# RFP.net
KiCad netlist of a schematic drawn in EAGLE
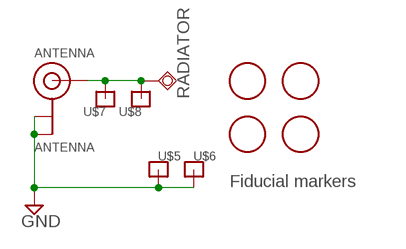
[diagram p0: schematic, sheet 1]

(export (version "E")
  (design (tool "Eeschema 10.0.6"))
  (components
    (comp (ref "ANTENNA")
      (value "ANTENNA")
      (footprint "eagle-import:U.FL")
      (libsource (lib "eagle-import") (part "ANTENNA_U.FL"))
    )
    (comp (ref "FD1")
      (value "FIDUCIAL")
      (footprint "eagle-import:FIDUCIAL_1MM")
      (libsource (lib "eagle-import") (part "FIDUCIAL"))
    )
    (comp (ref "FD2")
      (value "FIDUCIAL")
      (footprint "eagle-import:FIDUCIAL_1MM")
      (libsource (lib "eagle-import") (part "FIDUCIAL"))
    )
    (comp (ref "FD3")
      (value "FIDUCIAL")
      (footprint "eagle-import:FIDUCIAL_1MM")
      (libsource (lib "eagle-import") (part "FIDUCIAL"))
    )
    (comp (ref "FD4")
      (value "FIDUCIAL")
      (footprint "eagle-import:FIDUCIAL_1MM")
      (libsource (lib "eagle-import") (part "FIDUCIAL"))
    )
    (comp (ref "RADIATOR")
      (value "TPSQTP20SQ")
      (footprint "eagle-import:TP20SQ")
      (libsource (lib "eagle-import") (part "TPSQTP20SQ"))
    )
    (comp (ref "U$5")
      (value "2MMPILLAR")
      (footprint "eagle-import:2MMPILLAR")
      (libsource (lib "eagle-import") (part "2MMPILLAR"))
    )
    (comp (ref "U$6")
      (value "2MMPILLAR")
      (footprint "eagle-import:2MMPILLAR")
      (libsource (lib "eagle-import") (part "2MMPILLAR"))
    )
    (comp (ref "U$7")
      (value "2MMPILLAR")
      (footprint "eagle-import:2MMPILLAR")
      (libsource (lib "eagle-import") (part "2MMPILLAR"))
    )
    (comp (ref "U$8")
      (value "2MMPILLAR")
      (footprint "eagle-import:2MMPILLAR")
      (libsource (lib "eagle-import") (part "2MMPILLAR"))
    )
  )
  (nets
    (net (code "1") (name "GND") (class "Default")
      (node (ref "ANTENNA") (pin "1") (pinfunction "GND_1") (pintype "passive"))
      (node (ref "ANTENNA") (pin "2") (pinfunction "GND_2") (pintype "passive"))
      (node (ref "U$5") (pin "P$1") (pinfunction "P$1_P$1") (pintype "bidirectional"))
      (node (ref "U$6") (pin "P$1") (pinfunction "P$1_P$1") (pintype "bidirectional"))
    )
    (net (code "2") (name "Net-(ANTENNA-SIGNAL)") (class "Default")
      (node (ref "ANTENNA") (pin "3") (pinfunction "SIGNAL_3") (pintype "passive"))
      (node (ref "RADIATOR") (pin "TP") (pinfunction "TP_TP") (pintype "input"))
      (node (ref "U$7") (pin "P$1") (pinfunction "P$1_P$1") (pintype "bidirectional"))
      (node (ref "U$8") (pin "P$1") (pinfunction "P$1_P$1") (pintype "bidirectional"))
    )
  )
)
